# Un_ENC28J60.net
KiCad netlist of a schematic drawn in EAGLE
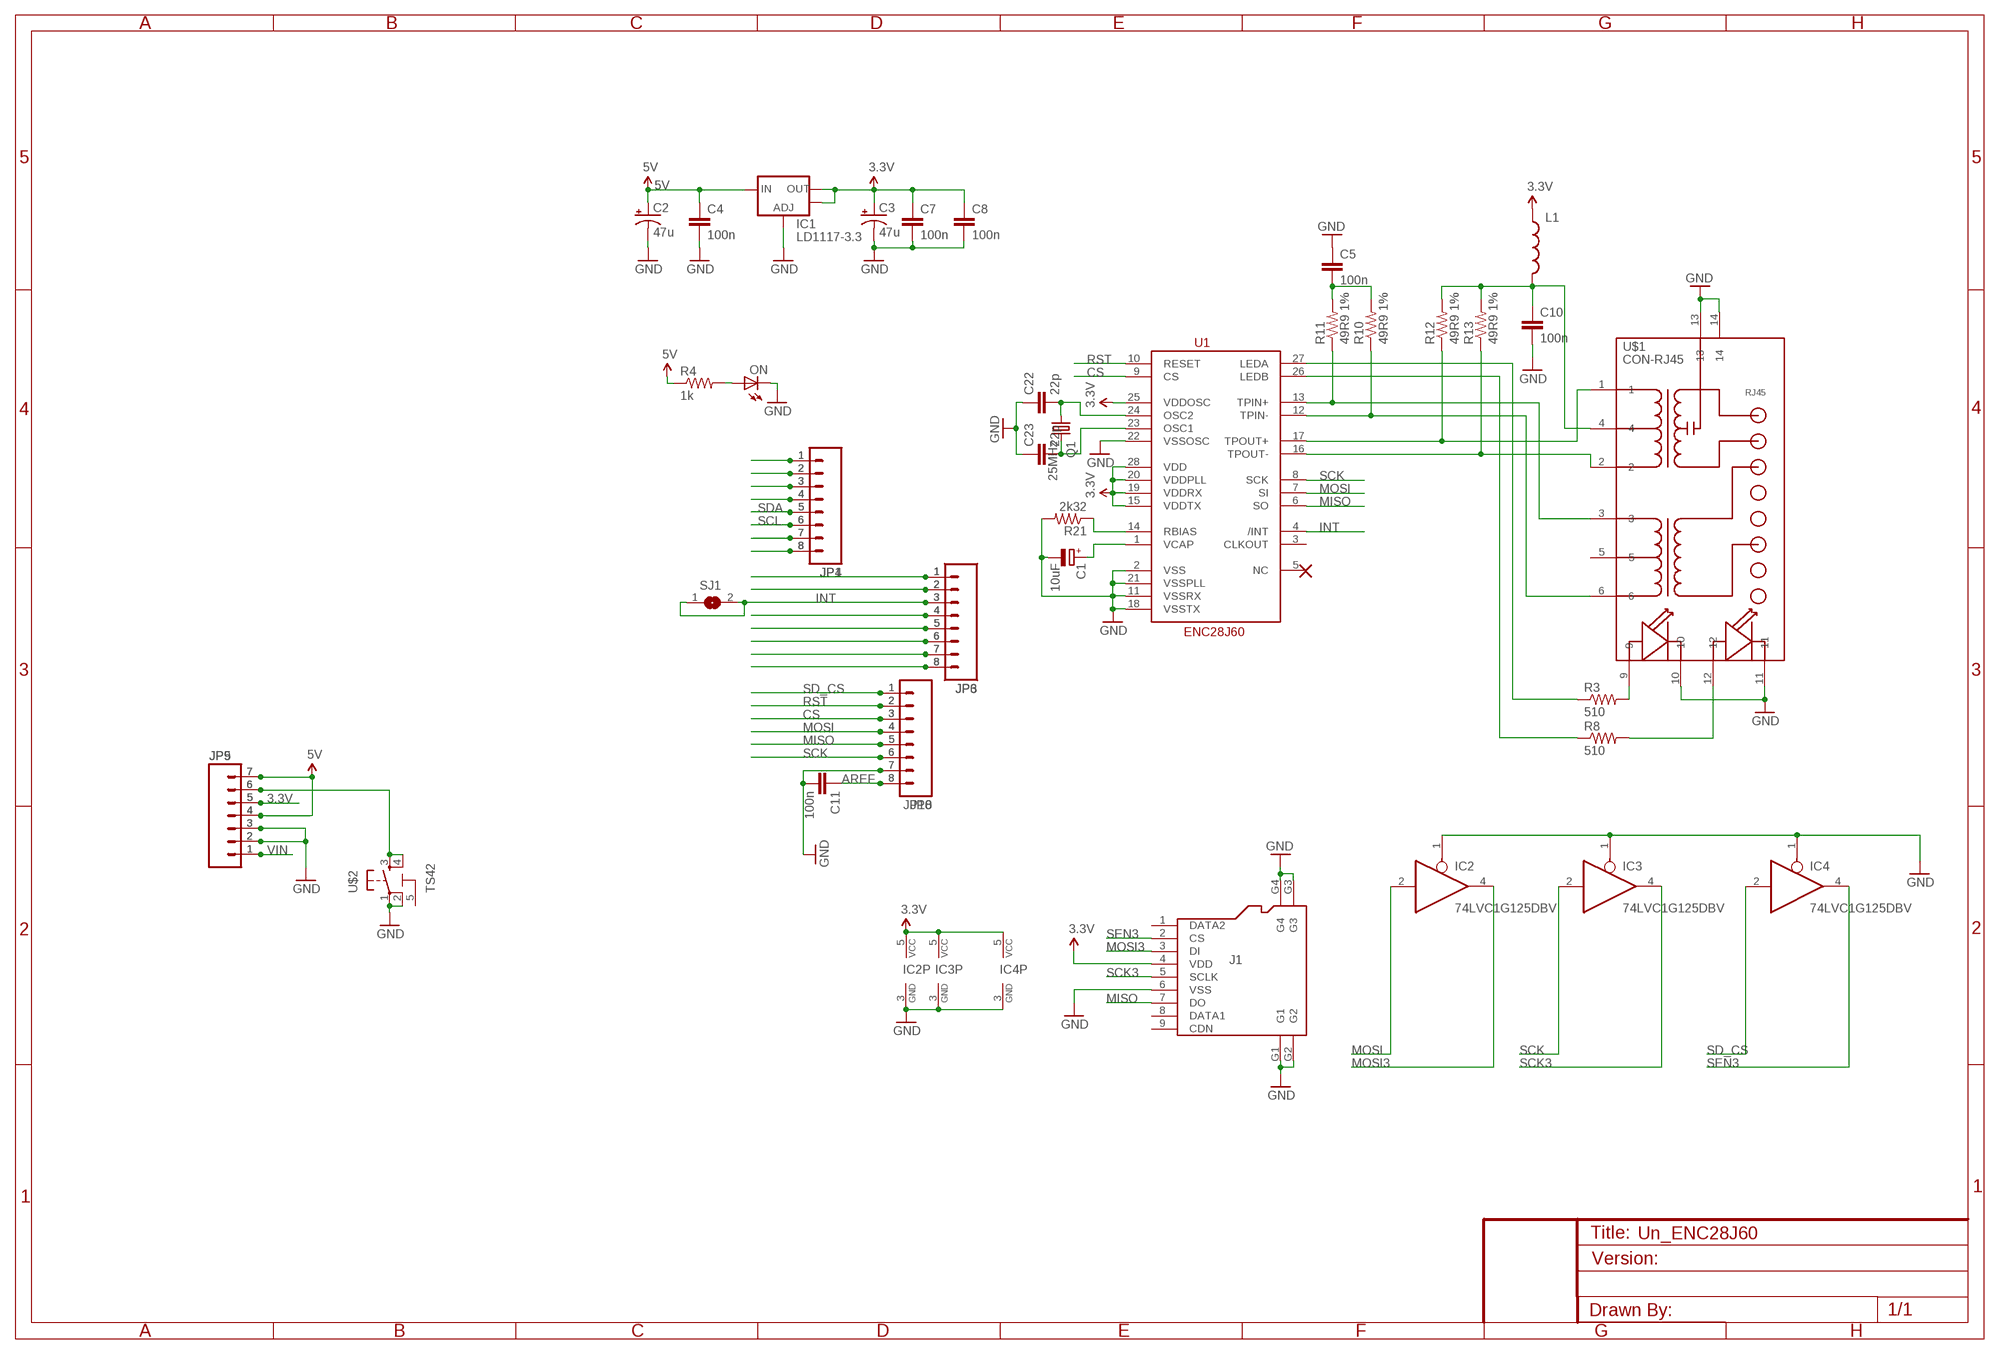
[diagram p0: schematic, sheet 1]

(export (version "E")
  (design (tool "Eeschema 10.0.6"))
  (components
    (comp (ref "C1")
      (value "10uF")
      (footprint "eagle-import:SMC_A")
      (libsource (lib "eagle-import") (part "CAP_POLSMC_A"))
    )
    (comp (ref "C2")
      (value "47u")
      (footprint "eagle-import:PANASONIC_D")
      (libsource (lib "eagle-import") (part "CAP_POLD"))
    )
    (comp (ref "C3")
      (value "47u")
      (footprint "eagle-import:PANASONIC_D")
      (libsource (lib "eagle-import") (part "CAP_POLD"))
    )
    (comp (ref "C4")
      (value "100n")
      (footprint "eagle-import:0603-CAP")
      (libsource (lib "eagle-import") (part "CAP0603-CAP"))
    )
    (comp (ref "C5")
      (value "100n")
      (footprint "eagle-import:0603-CAP")
      (libsource (lib "eagle-import") (part "CAP0603-CAP"))
    )
    (comp (ref "C7")
      (value "100n")
      (footprint "eagle-import:0603-CAP")
      (libsource (lib "eagle-import") (part "CAP0603-CAP"))
    )
    (comp (ref "C8")
      (value "100n")
      (footprint "eagle-import:0603-CAP")
      (libsource (lib "eagle-import") (part "CAP0603-CAP"))
    )
    (comp (ref "C10")
      (value "100n")
      (footprint "eagle-import:0603-CAP")
      (libsource (lib "eagle-import") (part "CAP0603-CAP"))
    )
    (comp (ref "C11")
      (value "100n")
      (footprint "eagle-import:0603-CAP")
      (libsource (lib "eagle-import") (part "CAP0603-CAP"))
    )
    (comp (ref "C22")
      (value "22p")
      (footprint "eagle-import:0805")
      (libsource (lib "eagle-import") (part "CAP0805"))
    )
    (comp (ref "C23")
      (value "22p")
      (footprint "eagle-import:0805")
      (libsource (lib "eagle-import") (part "CAP0805"))
    )
    (comp (ref "IC1")
      (value "LD1117-3.3")
      (footprint "eagle-import:SOT223")
      (libsource (lib "eagle-import") (part "V_REG_LM1117SOT223"))
    )
    (comp (ref "IC2")
      (value "74LVC1G125DBV")
      (footprint "eagle-import:SOT23-5")
      (libsource (lib "eagle-import") (part "741G125DBVLVC"))
    )
    (comp (ref "IC3")
      (value "74LVC1G125DBV")
      (footprint "eagle-import:SOT23-5")
      (libsource (lib "eagle-import") (part "741G125DBVLVC"))
    )
    (comp (ref "IC4")
      (value "74LVC1G125DBV")
      (footprint "eagle-import:SOT23-5")
      (libsource (lib "eagle-import") (part "741G125DBVLVC"))
    )
    (comp (ref "J1")
      (value "HOLDER-MICROSD-9P")
      (footprint "eagle-import:9P-SMD-W_-RING")
      (libsource (lib "eagle-import") (part "HOLDER-MICROSD-9P"))
    )
    (comp (ref "JP1")
      (value "M081X08")
      (footprint "eagle-import:1X08")
      (libsource (lib "eagle-import") (part "M081X08"))
    )
    (comp (ref "JP3")
      (value "M08")
      (footprint "eagle-import:1X08")
      (libsource (lib "eagle-import") (part "M08"))
    )
    (comp (ref "JP4")
      (value "M081X08")
      (footprint "eagle-import:1X08")
      (libsource (lib "eagle-import") (part "M081X08"))
    )
    (comp (ref "JP5")
      (value "M07")
      (footprint "eagle-import:1X07")
      (libsource (lib "eagle-import") (part "M07"))
    )
    (comp (ref "JP6")
      (value "M08")
      (footprint "eagle-import:1X08")
      (libsource (lib "eagle-import") (part "M08"))
    )
    (comp (ref "JP8")
      (value "M08")
      (footprint "eagle-import:1X08")
      (libsource (lib "eagle-import") (part "M08"))
    )
    (comp (ref "JP9")
      (value "M07")
      (footprint "eagle-import:1X07")
      (libsource (lib "eagle-import") (part "M07"))
    )
    (comp (ref "JP10")
      (value "M08")
      (footprint "eagle-import:1X08")
      (libsource (lib "eagle-import") (part "M08"))
    )
    (comp (ref "L1")
      (value "INDUCTOR0805")
      (footprint "eagle-import:0805")
      (libsource (lib "eagle-import") (part "INDUCTOR0805"))
    )
    (comp (ref "ON")
      (value "LED0805")
      (footprint "eagle-import:LED-0805")
      (libsource (lib "eagle-import") (part "LED0805"))
    )
    (comp (ref "Q1")
      (value "25MHz")
      (footprint "eagle-import:HC49US")
      (libsource (lib "eagle-import") (part "CRYSTALHC49US"))
    )
    (comp (ref "R3")
      (value "510")
      (footprint "eagle-import:0805")
      (libsource (lib "eagle-import") (part "RESISTOR0805-RES"))
    )
    (comp (ref "R4")
      (value "1k")
      (footprint "eagle-import:0805")
      (libsource (lib "eagle-import") (part "RESISTOR0805-RES"))
    )
    (comp (ref "R8")
      (value "510")
      (footprint "eagle-import:0805")
      (libsource (lib "eagle-import") (part "RESISTOR0805-RES"))
    )
    (comp (ref "R10")
      (value "49R9 1%")
      (footprint "eagle-import:0805")
      (libsource (lib "eagle-import") (part "RESISTOR0805-RES"))
    )
    (comp (ref "R11")
      (value "49R9 1%")
      (footprint "eagle-import:0805")
      (libsource (lib "eagle-import") (part "RESISTOR0805-RES"))
    )
    (comp (ref "R12")
      (value "49R9 1%")
      (footprint "eagle-import:0805")
      (libsource (lib "eagle-import") (part "RESISTOR0805-RES"))
    )
    (comp (ref "R13")
      (value "49R9 1%")
      (footprint "eagle-import:0805")
      (libsource (lib "eagle-import") (part "RESISTOR0805-RES"))
    )
    (comp (ref "R21")
      (value "2k32")
      (footprint "eagle-import:0805")
      (libsource (lib "eagle-import") (part "RESISTOR0805-RES"))
    )
    (comp (ref "SJ1") (value "SJ") (footprint "eagle-import:SJ") (libsource (lib "eagle-import") (part "SJ")))
    (comp (ref "U$1")
      (value "CON-RJ45")
      (footprint "eagle-import:CONNECTER_HR911105A")
      (libsource (lib "eagle-import") (part "CON-RJ45"))
    )
    (comp (ref "U$2")
      (value "TS42")
      (footprint "eagle-import:TS42")
      (libsource (lib "eagle-import") (part "TS42"))
    )
    (comp (ref "U1")
      (value "ENC28J60")
      (footprint "eagle-import:SSOP28DB")
      (libsource (lib "eagle-import") (part "ENC28J60"))
    )
  )
  (nets
    (net (code "1") (name "/AREF") (class "Default")
      (node (ref "C11") (pin "1") (pinfunction "1_1") (pintype "passive"))
      (node (ref "JP10") (pin "8") (pinfunction "8_8") (pintype "passive"))
      (node (ref "JP8") (pin "8") (pinfunction "8_8") (pintype "passive"))
    )
    (net (code "2") (name "/CS") (class "Default")
      (node (ref "JP10") (pin "3") (pinfunction "3_3") (pintype "passive"))
      (node (ref "JP8") (pin "3") (pinfunction "3_3") (pintype "passive"))
      (node (ref "U1") (pin "9") (pinfunction "CS_9") (pintype "bidirectional"))
    )
    (net (code "3") (name "/INT") (class "Default")
      (node (ref "JP3") (pin "3") (pinfunction "3_3") (pintype "passive"))
      (node (ref "JP6") (pin "3") (pinfunction "3_3") (pintype "passive"))
      (node (ref "SJ1") (pin "1") (pinfunction "1_1") (pintype "passive"))
      (node (ref "SJ1") (pin "2") (pinfunction "2_2") (pintype "passive"))
      (node (ref "U1") (pin "4") (pinfunction "/INT_4") (pintype "bidirectional"))
    )
    (net (code "4") (name "/MISO") (class "Default")
      (node (ref "J1") (pin "7") (pinfunction "DO_7") (pintype "bidirectional"))
      (node (ref "JP10") (pin "5") (pinfunction "5_5") (pintype "passive"))
      (node (ref "JP8") (pin "5") (pinfunction "5_5") (pintype "passive"))
      (node (ref "U1") (pin "6") (pinfunction "SO_6") (pintype "bidirectional"))
    )
    (net (code "5") (name "/MOSI") (class "Default")
      (node (ref "IC2") (pin "2") (pinfunction "I_2") (pintype "input"))
      (node (ref "JP10") (pin "4") (pinfunction "4_4") (pintype "passive"))
      (node (ref "JP8") (pin "4") (pinfunction "4_4") (pintype "passive"))
      (node (ref "U1") (pin "7") (pinfunction "SI_7") (pintype "bidirectional"))
    )
    (net (code "6") (name "/MOSI3") (class "Default")
      (node (ref "IC2") (pin "4") (pinfunction "O_4") (pintype "tri_state"))
      (node (ref "J1") (pin "3") (pinfunction "DI_3") (pintype "bidirectional"))
    )
    (net (code "7") (name "/RST") (class "Default")
      (node (ref "JP10") (pin "2") (pinfunction "2_2") (pintype "passive"))
      (node (ref "JP8") (pin "2") (pinfunction "2_2") (pintype "passive"))
      (node (ref "U1") (pin "10") (pinfunction "RESET_10") (pintype "bidirectional"))
    )
    (net (code "8") (name "/SCK") (class "Default")
      (node (ref "IC3") (pin "2") (pinfunction "I_2") (pintype "input"))
      (node (ref "JP10") (pin "6") (pinfunction "6_6") (pintype "passive"))
      (node (ref "JP8") (pin "6") (pinfunction "6_6") (pintype "passive"))
      (node (ref "U1") (pin "8") (pinfunction "SCK_8") (pintype "bidirectional"))
    )
    (net (code "9") (name "/SCK3") (class "Default")
      (node (ref "IC3") (pin "4") (pinfunction "O_4") (pintype "tri_state"))
      (node (ref "J1") (pin "5") (pinfunction "SCLK_5") (pintype "bidirectional"))
    )
    (net (code "10") (name "/SCL") (class "Default")
      (node (ref "JP1") (pin "6") (pinfunction "6_6") (pintype "passive"))
      (node (ref "JP4") (pin "6") (pinfunction "6_6") (pintype "passive"))
    )
    (net (code "11") (name "/SDA") (class "Default")
      (node (ref "JP1") (pin "5") (pinfunction "5_5") (pintype "passive"))
      (node (ref "JP4") (pin "5") (pinfunction "5_5") (pintype "passive"))
    )
    (net (code "12") (name "/SD_CS") (class "Default")
      (node (ref "IC4") (pin "2") (pinfunction "I_2") (pintype "input"))
      (node (ref "JP10") (pin "1") (pinfunction "1_1") (pintype "passive"))
      (node (ref "JP8") (pin "1") (pinfunction "1_1") (pintype "passive"))
    )
    (net (code "13") (name "/SEN3") (class "Default")
      (node (ref "IC4") (pin "4") (pinfunction "O_4") (pintype "tri_state"))
      (node (ref "J1") (pin "2") (pinfunction "CS_2") (pintype "bidirectional"))
    )
    (net (code "14") (name "/VIN") (class "Default")
      (node (ref "JP5") (pin "1") (pinfunction "1_1") (pintype "passive"))
      (node (ref "JP9") (pin "1") (pinfunction "1_1") (pintype "passive"))
    )
    (net (code "15") (name "3.3V") (class "Default")
      (node (ref "C3") (pin "+") (pinfunction "+_+") (pintype "passive"))
      (node (ref "C7") (pin "1") (pinfunction "1_1") (pintype "passive"))
      (node (ref "C8") (pin "1") (pinfunction "1_1") (pintype "passive"))
      (node (ref "IC1") (pin "2") (pinfunction "OUT_2") (pintype "output"))
      (node (ref "IC1") (pin "4") (pinfunction "OUT_4") (pintype "output"))
      (node (ref "IC2") (pin "5") (pinfunction "VCC_5") (pintype "power_in"))
      (node (ref "IC3") (pin "5") (pinfunction "VCC_5") (pintype "power_in"))
      (node (ref "IC4") (pin "5") (pinfunction "VCC_5") (pintype "power_in"))
      (node (ref "J1") (pin "4") (pinfunction "VDD_4") (pintype "bidirectional"))
      (node (ref "JP5") (pin "5") (pinfunction "5_5") (pintype "passive"))
      (node (ref "JP9") (pin "5") (pinfunction "5_5") (pintype "passive"))
      (node (ref "L1") (pin "1") (pinfunction "1_1") (pintype "passive"))
      (node (ref "U1") (pin "15") (pinfunction "VDDTX_15") (pintype "bidirectional"))
      (node (ref "U1") (pin "19") (pinfunction "VDDRX_19") (pintype "bidirectional"))
      (node (ref "U1") (pin "20") (pinfunction "VDDPLL_20") (pintype "bidirectional"))
      (node (ref "U1") (pin "25") (pinfunction "VDDOSC_25") (pintype "bidirectional"))
      (node (ref "U1") (pin "28") (pinfunction "VDD_28") (pintype "bidirectional"))
    )
    (net (code "16") (name "5V") (class "Default")
      (node (ref "C2") (pin "+") (pinfunction "+_+") (pintype "passive"))
      (node (ref "C4") (pin "1") (pinfunction "1_1") (pintype "passive"))
      (node (ref "IC1") (pin "3") (pinfunction "IN_3") (pintype "input"))
      (node (ref "JP5") (pin "4") (pinfunction "4_4") (pintype "passive"))
      (node (ref "JP5") (pin "7") (pinfunction "7_7") (pintype "passive"))
      (node (ref "JP9") (pin "4") (pinfunction "4_4") (pintype "passive"))
      (node (ref "JP9") (pin "7") (pinfunction "7_7") (pintype "passive"))
      (node (ref "R4") (pin "1") (pinfunction "1_1") (pintype "passive"))
    )
    (net (code "17") (name "GND") (class "Default")
      (node (ref "C1") (pin "-") (pinfunction "-_-") (pintype "passive"))
      (node (ref "C10") (pin "2") (pinfunction "2_2") (pintype "passive"))
      (node (ref "C11") (pin "2") (pinfunction "2_2") (pintype "passive"))
      (node (ref "C2") (pin "-") (pinfunction "-_-") (pintype "passive"))
      (node (ref "C22") (pin "1") (pinfunction "1_1") (pintype "passive"))
      (node (ref "C23") (pin "1") (pinfunction "1_1") (pintype "passive"))
      (node (ref "C3") (pin "-") (pinfunction "-_-") (pintype "passive"))
      (node (ref "C4") (pin "2") (pinfunction "2_2") (pintype "passive"))
      (node (ref "C5") (pin "1") (pinfunction "1_1") (pintype "passive"))
      (node (ref "C7") (pin "2") (pinfunction "2_2") (pintype "passive"))
      (node (ref "C8") (pin "2") (pinfunction "2_2") (pintype "passive"))
      (node (ref "IC1") (pin "1") (pinfunction "ADJ_1") (pintype "input"))
      (node (ref "IC2") (pin "1") (pinfunction "OE_1") (pintype "input"))
      (node (ref "IC2") (pin "3") (pinfunction "GND_3") (pintype "power_in"))
      (node (ref "IC3") (pin "1") (pinfunction "OE_1") (pintype "input"))
      (node (ref "IC3") (pin "3") (pinfunction "GND_3") (pintype "power_in"))
      (node (ref "IC4") (pin "1") (pinfunction "OE_1") (pintype "input"))
      (node (ref "IC4") (pin "3") (pinfunction "GND_3") (pintype "power_in"))
      (node (ref "J1") (pin "6") (pinfunction "VSS_6") (pintype "bidirectional"))
      (node (ref "J1") (pin "G1") (pinfunction "G1_G1") (pintype "bidirectional"))
      (node (ref "J1") (pin "G2") (pinfunction "G2_G2") (pintype "bidirectional"))
      (node (ref "J1") (pin "G3") (pinfunction "G3_G3") (pintype "bidirectional"))
      (node (ref "J1") (pin "G4") (pinfunction "G4_G4") (pintype "bidirectional"))
      (node (ref "JP10") (pin "7") (pinfunction "7_7") (pintype "passive"))
      (node (ref "JP5") (pin "2") (pinfunction "2_2") (pintype "passive"))
      (node (ref "JP5") (pin "3") (pinfunction "3_3") (pintype "passive"))
      (node (ref "JP8") (pin "7") (pinfunction "7_7") (pintype "passive"))
      (node (ref "JP9") (pin "2") (pinfunction "2_2") (pintype "passive"))
      (node (ref "JP9") (pin "3") (pinfunction "3_3") (pintype "passive"))
      (node (ref "ON") (pin "2") (pinfunction "C_2") (pintype "passive"))
      (node (ref "R21") (pin "2") (pinfunction "2_2") (pintype "passive"))
      (node (ref "U$1") (pin "10") (pinfunction "10_10") (pintype "bidirectional"))
      (node (ref "U$1") (pin "11") (pinfunction "11_11") (pintype "bidirectional"))
      (node (ref "U$1") (pin "13") (pinfunction "13_13") (pintype "bidirectional"))
      (node (ref "U$1") (pin "14") (pinfunction "14_14") (pintype "bidirectional"))
      (node (ref "U$2") (pin "1") (pinfunction "1_1") (pintype "passive"))
      (node (ref "U$2") (pin "2") (pinfunction "2_2") (pintype "passive"))
      (node (ref "U1") (pin "11") (pinfunction "VSSRX_11") (pintype "bidirectional"))
      (node (ref "U1") (pin "18") (pinfunction "VSSTX_18") (pintype "bidirectional"))
      (node (ref "U1") (pin "2") (pinfunction "VSS_2") (pintype "bidirectional"))
      (node (ref "U1") (pin "21") (pinfunction "VSSPLL_21") (pintype "bidirectional"))
      (node (ref "U1") (pin "22") (pinfunction "VSSOSC_22") (pintype "bidirectional"))
    )
    (net (code "18") (name "Net-(C5-Pad2)") (class "Default")
      (node (ref "C5") (pin "2") (pinfunction "2_2") (pintype "passive"))
      (node (ref "R10") (pin "2") (pinfunction "2_2") (pintype "passive"))
      (node (ref "R11") (pin "2") (pinfunction "2_2") (pintype "passive"))
    )
    (net (code "19") (name "Net-(C10-Pad1)") (class "Default")
      (node (ref "C10") (pin "1") (pinfunction "1_1") (pintype "passive"))
      (node (ref "L1") (pin "2") (pinfunction "2_2") (pintype "passive"))
      (node (ref "R12") (pin "2") (pinfunction "2_2") (pintype "passive"))
      (node (ref "R13") (pin "2") (pinfunction "2_2") (pintype "passive"))
      (node (ref "U$1") (pin "4") (pinfunction "4_4") (pintype "bidirectional"))
    )
    (net (code "20") (name "Net-(JP1-Pad1)") (class "Default")
      (node (ref "JP1") (pin "1") (pinfunction "1_1") (pintype "passive"))
      (node (ref "JP4") (pin "1") (pinfunction "1_1") (pintype "passive"))
    )
    (net (code "21") (name "Net-(JP1-Pad2)") (class "Default")
      (node (ref "JP1") (pin "2") (pinfunction "2_2") (pintype "passive"))
      (node (ref "JP4") (pin "2") (pinfunction "2_2") (pintype "passive"))
    )
    (net (code "22") (name "Net-(JP1-Pad3)") (class "Default")
      (node (ref "JP1") (pin "3") (pinfunction "3_3") (pintype "passive"))
      (node (ref "JP4") (pin "3") (pinfunction "3_3") (pintype "passive"))
    )
    (net (code "23") (name "Net-(JP1-Pad4)") (class "Default")
      (node (ref "JP1") (pin "4") (pinfunction "4_4") (pintype "passive"))
      (node (ref "JP4") (pin "4") (pinfunction "4_4") (pintype "passive"))
    )
    (net (code "24") (name "Net-(JP1-Pad7)") (class "Default")
      (node (ref "JP1") (pin "7") (pinfunction "7_7") (pintype "passive"))
      (node (ref "JP4") (pin "7") (pinfunction "7_7") (pintype "passive"))
    )
    (net (code "25") (name "Net-(JP1-Pad8)") (class "Default")
      (node (ref "JP1") (pin "8") (pinfunction "8_8") (pintype "passive"))
      (node (ref "JP4") (pin "8") (pinfunction "8_8") (pintype "passive"))
    )
    (net (code "26") (name "Net-(JP3-Pad1)") (class "Default")
      (node (ref "JP3") (pin "1") (pinfunction "1_1") (pintype "passive"))
      (node (ref "JP6") (pin "1") (pinfunction "1_1") (pintype "passive"))
    )
    (net (code "27") (name "Net-(JP3-Pad2)") (class "Default")
      (node (ref "JP3") (pin "2") (pinfunction "2_2") (pintype "passive"))
      (node (ref "JP6") (pin "2") (pinfunction "2_2") (pintype "passive"))
    )
    (net (code "28") (name "Net-(JP3-Pad4)") (class "Default")
      (node (ref "JP3") (pin "4") (pinfunction "4_4") (pintype "passive"))
      (node (ref "JP6") (pin "4") (pinfunction "4_4") (pintype "passive"))
    )
    (net (code "29") (name "Net-(JP3-Pad5)") (class "Default")
      (node (ref "JP3") (pin "5") (pinfunction "5_5") (pintype "passive"))
      (node (ref "JP6") (pin "5") (pinfunction "5_5") (pintype "passive"))
    )
    (net (code "30") (name "Net-(JP3-Pad6)") (class "Default")
      (node (ref "JP3") (pin "6") (pinfunction "6_6") (pintype "passive"))
      (node (ref "JP6") (pin "6") (pinfunction "6_6") (pintype "passive"))
    )
    (net (code "31") (name "Net-(JP3-Pad7)") (class "Default")
      (node (ref "JP3") (pin "7") (pinfunction "7_7") (pintype "passive"))
      (node (ref "JP6") (pin "7") (pinfunction "7_7") (pintype "passive"))
    )
    (net (code "32") (name "Net-(JP3-Pad8)") (class "Default")
      (node (ref "JP3") (pin "8") (pinfunction "8_8") (pintype "passive"))
      (node (ref "JP6") (pin "8") (pinfunction "8_8") (pintype "passive"))
    )
    (net (code "33") (name "Net-(JP5-Pad6)") (class "Default")
      (node (ref "JP5") (pin "6") (pinfunction "6_6") (pintype "passive"))
      (node (ref "JP9") (pin "6") (pinfunction "6_6") (pintype "passive"))
      (node (ref "U$2") (pin "3") (pinfunction "3_3") (pintype "passive"))
      (node (ref "U$2") (pin "4") (pinfunction "4_4") (pintype "passive"))
    )
    (net (code "34") (name "Net-(ON-A)") (class "Default")
      (node (ref "ON") (pin "1") (pinfunction "A_1") (pintype "passive"))
      (node (ref "R4") (pin "2") (pinfunction "2_2") (pintype "passive"))
    )
    (net (code "35") (name "Net-(R3-Pad2)") (class "Default")
      (node (ref "R3") (pin "2") (pinfunction "2_2") (pintype "passive"))
      (node (ref "U$1") (pin "9") (pinfunction "9_9") (pintype "bidirectional"))
    )
    (net (code "36") (name "Net-(R8-Pad2)") (class "Default")
      (node (ref "R8") (pin "2") (pinfunction "2_2") (pintype "passive"))
      (node (ref "U$1") (pin "12") (pinfunction "12_12") (pintype "bidirectional"))
    )
    (net (code "37") (name "Net-(U1-LEDA)") (class "Default")
      (node (ref "R3") (pin "1") (pinfunction "1_1") (pintype "passive"))
      (node (ref "U1") (pin "27") (pinfunction "LEDA_27") (pintype "bidirectional"))
    )
    (net (code "38") (name "Net-(U1-LEDB)") (class "Default")
      (node (ref "R8") (pin "1") (pinfunction "1_1") (pintype "passive"))
      (node (ref "U1") (pin "26") (pinfunction "LEDB_26") (pintype "bidirectional"))
    )
    (net (code "39") (name "Net-(U1-OSC1)") (class "Default")
      (node (ref "C23") (pin "2") (pinfunction "2_2") (pintype "passive"))
      (node (ref "Q1") (pin "2") (pinfunction "2_2") (pintype "passive"))
      (node (ref "U1") (pin "23") (pinfunction "OSC1_23") (pintype "bidirectional"))
    )
    (net (code "40") (name "Net-(U1-OSC2)") (class "Default")
      (node (ref "C22") (pin "2") (pinfunction "2_2") (pintype "passive"))
      (node (ref "Q1") (pin "1") (pinfunction "1_1") (pintype "passive"))
      (node (ref "U1") (pin "24") (pinfunction "OSC2_24") (pintype "bidirectional"))
    )
    (net (code "41") (name "Net-(U1-RBIAS)") (class "Default")
      (node (ref "R21") (pin "1") (pinfunction "1_1") (pintype "passive"))
      (node (ref "U1") (pin "14") (pinfunction "RBIAS_14") (pintype "bidirectional"))
    )
    (net (code "42") (name "Net-(U1-TPIN+)") (class "Default")
      (node (ref "R11") (pin "1") (pinfunction "1_1") (pintype "passive"))
      (node (ref "U$1") (pin "3") (pinfunction "3_3") (pintype "bidirectional"))
      (node (ref "U1") (pin "13") (pinfunction "TPIN+_13") (pintype "bidirectional"))
    )
    (net (code "43") (name "Net-(U1-TPIN-)") (class "Default")
      (node (ref "R10") (pin "1") (pinfunction "1_1") (pintype "passive"))
      (node (ref "U$1") (pin "6") (pinfunction "6_6") (pintype "bidirectional"))
      (node (ref "U1") (pin "12") (pinfunction "TPIN-_12") (pintype "bidirectional"))
    )
    (net (code "44") (name "Net-(U1-TPOUT+)") (class "Default")
      (node (ref "R12") (pin "1") (pinfunction "1_1") (pintype "passive"))
      (node (ref "U$1") (pin "1") (pinfunction "1_1") (pintype "bidirectional"))
      (node (ref "U1") (pin "17") (pinfunction "TPOUT+_17") (pintype "bidirectional"))
    )
    (net (code "45") (name "Net-(U1-TPOUT-)") (class "Default")
      (node (ref "R13") (pin "1") (pinfunction "1_1") (pintype "passive"))
      (node (ref "U$1") (pin "2") (pinfunction "2_2") (pintype "bidirectional"))
      (node (ref "U1") (pin "16") (pinfunction "TPOUT-_16") (pintype "bidirectional"))
    )
    (net (code "46") (name "Net-(U1-VCAP)") (class "Default")
      (node (ref "C1") (pin "+") (pinfunction "+_+") (pintype "passive"))
      (node (ref "U1") (pin "1") (pinfunction "VCAP_1") (pintype "bidirectional"))
    )
    (net (code "47") (name "unconnected-(J1-CDN-Pad9)") (class "Default")
      (node (ref "J1") (pin "9") (pinfunction "CDN_9") (pintype "bidirectional"))
    )
    (net (code "48") (name "unconnected-(J1-DATA1-Pad8)") (class "Default")
      (node (ref "J1") (pin "8") (pinfunction "DATA1_8") (pintype "bidirectional"))
    )
    (net (code "49") (name "unconnected-(J1-DATA2-Pad1)") (class "Default")
      (node (ref "J1") (pin "1") (pinfunction "DATA2_1") (pintype "bidirectional"))
    )
    (net (code "50") (name "unconnected-(U$1-Pad5)") (class "Default")
      (node (ref "U$1") (pin "5") (pinfunction "5_5") (pintype "bidirectional"))
    )
    (net (code "51") (name "unconnected-(U$2-Pad5)") (class "Default")
      (node (ref "U$2") (pin "5") (pinfunction "5_5") (pintype "passive"))
    )
    (net (code "52") (name "unconnected-(U1-CLKOUT-Pad3)") (class "Default")
      (node (ref "U1") (pin "3") (pinfunction "CLKOUT_3") (pintype "bidirectional"))
    )
    (net (code "53") (name "unconnected-(U1-NC-Pad5)") (class "Default")
      (node (ref "U1") (pin "5") (pinfunction "NC_5") (pintype "bidirectional"))
    )
  )
)
